# Core.net
KiCad netlist of a schematic drawn in Altium Designer
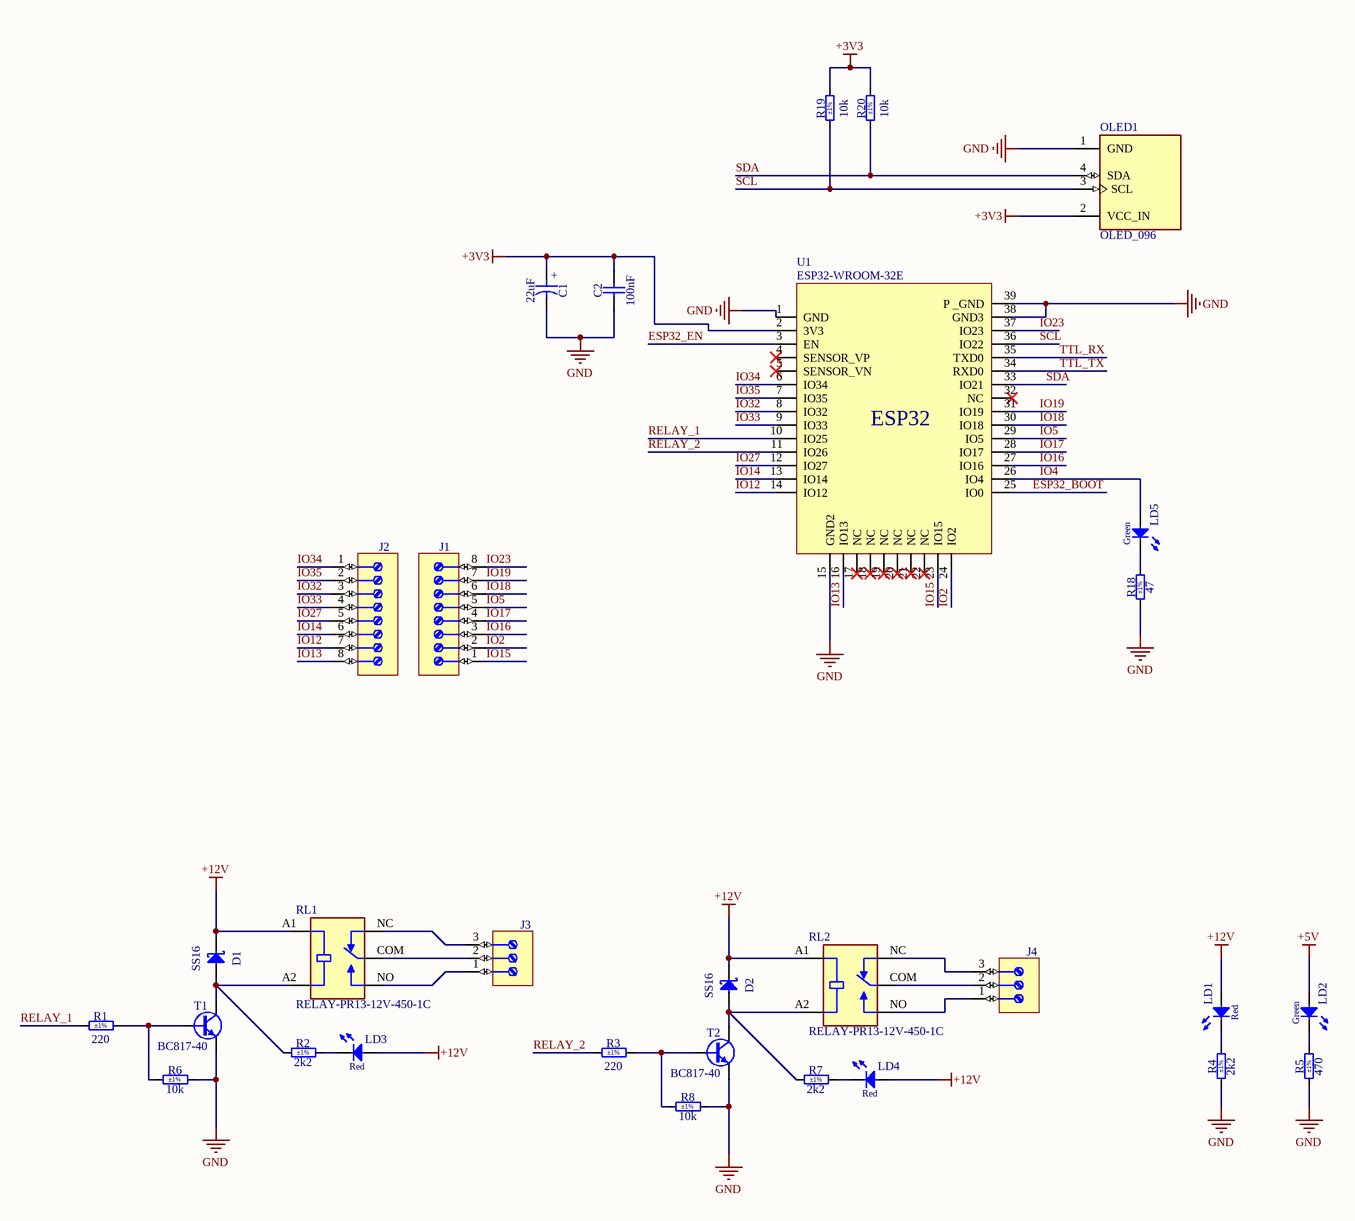
[diagram p0: Core.SchDoc]

(export (version "E")
  (design (tool "Eeschema 10.0.6"))
  (components
    (comp (ref "C1")
      (value "22uF")
      (footprint "CAPMP3528X210N")
      (description "Polarised capacitor")
      (fields
        (field (name "PART NUMBER") "CTE3528-21_22UF_10V_10%_LESR0700")
        (field (name "VOLTAGE") "10V")
        (field (name "AUTHOR") "CERN DEM JLC")
      )
      (libsource (lib "Capacitors") (part "Capacitor - polarized"))
    )
    (comp (ref "C2")
      (value "100nF")
      (footprint "CAPC1608X87N")
      (description "Non-polarised capacitor")
      (fields
        (field (name "PART NUMBER") "CC0603_100NF_50V_10%_X5R")
        (field (name "VOLTAGE") "50V")
        (field (name "AUTHOR") "CERN DEM MR")
      )
      (libsource (lib "Capacitors") (part "Capacitor - non polarized"))
    )
    (comp (ref "D1")
      (value "SS16")
      (footprint "DIOM5127X229N")
      (description "Schottky Diode")
      (fields
        (field (name "VOLTAGE") "60V")
        (field (name "POWER") "1A")
        (field (name "AUTHOR") "CERN DEM JLC")
      )
      (libsource (lib "ICs And Semiconductors") (part "Diode Schottky"))
    )
    (comp (ref "D2")
      (value "SS16")
      (footprint "DIOM5127X229N")
      (description "Schottky Diode")
      (fields
        (field (name "VOLTAGE") "60V")
        (field (name "POWER") "1A")
        (field (name "AUTHOR") "CERN DEM JLC")
      )
      (libsource (lib "ICs And Semiconductors") (part "Diode Schottky"))
    )
    (comp (ref "J1")
      (value "~")
      (footprint "PHOENIX_1715789")
      (description "Terminal Block, 8 Positions, Screw Connection")
      (fields
        (field (name "PART NUMBER") "PHOENIX_1715789")
        (field (name "MANUFACTURER") "PHOENIX CONTACT")
        (field (name "AUTHOR") "CERN DEM JMW")
      )
      (libsource (lib "") (part "Terminal Block_8 Positions_Screw Connection_1"))
    )
    (comp (ref "J2")
      (value "~")
      (footprint "PHOENIX_1715789")
      (description "Terminal Block, 8 Positions, Screw Connection")
      (fields
        (field (name "PART NUMBER") "PHOENIX_1715789")
        (field (name "MANUFACTURER") "PHOENIX CONTACT")
        (field (name "AUTHOR") "CERN DEM JMW")
      )
      (libsource (lib "Connectors") (part "Terminal Block_8 Positions_Screw Connection"))
    )
    (comp (ref "J3")
      (value "~")
      (footprint "PHOENIX_1715734")
      (description "Terminal Block, 3 Positions, Screw Connection")
      (fields
        (field (name "PART NUMBER") "PHOENIX_1715734")
        (field (name "MANUFACTURER") "PHOENIX CONTACT")
        (field (name "AUTHOR") "CERN DEM JLC")
      )
      (libsource (lib "Connectors") (part "Terminal Block_3 Positions_Screw Connection"))
    )
    (comp (ref "J4")
      (value "~")
      (footprint "PHOENIX_1715734")
      (description "Terminal Block, 3 Positions, Screw Connection")
      (fields
        (field (name "PART NUMBER") "PHOENIX_1715734")
        (field (name "MANUFACTURER") "PHOENIX CONTACT")
        (field (name "AUTHOR") "CERN DEM JLC")
      )
      (libsource (lib "Connectors") (part "Terminal Block_3 Positions_Screw Connection"))
    )
    (comp (ref "LD1")
      (value "Red")
      (footprint "LED_KINGBRIGHT_KPH-1608SURCK")
      (description "LED Red 1C 2A")
      (fields
        (field (name "PART NUMBER") "LED_KINGBRIGHT_KPH-1608SURCK")
        (field (name "MANUFACTURER") "KINGBRIGHT")
        (field (name "AUTHOR") "CERN DEM JLC")
      )
      (libsource (lib "ICs And Semiconductors") (part "LED Red 1C 2A"))
    )
    (comp (ref "LD2")
      (value "Green")
      (footprint "LED_KINGBRIGHT_KP-1608CGCK")
      (description "LED Green 1C 2A")
      (fields
        (field (name "PART NUMBER") "LED_KINGBRIGHT_KP-1608CGCK")
        (field (name "MANUFACTURER") "KINGBRIGHT")
        (field (name "AUTHOR") "CERN DEM HF")
      )
      (libsource (lib "ICs And Semiconductors") (part "LED Green 1C 2A"))
    )
    (comp (ref "LD3")
      (value "Red")
      (footprint "LED_KINGBRIGHT_KPH-1608SURCK")
      (description "LED Red 1C 2A")
      (fields
        (field (name "PART NUMBER") "LED_KINGBRIGHT_KPH-1608SURCK")
        (field (name "MANUFACTURER") "KINGBRIGHT")
        (field (name "AUTHOR") "CERN DEM JLC")
      )
      (libsource (lib "ICs And Semiconductors") (part "LED Red 1C 2A"))
    )
    (comp (ref "LD4")
      (value "Red")
      (footprint "LED_KINGBRIGHT_KPH-1608SURCK")
      (description "LED Red 1C 2A")
      (fields
        (field (name "PART NUMBER") "LED_KINGBRIGHT_KPH-1608SURCK")
        (field (name "MANUFACTURER") "KINGBRIGHT")
        (field (name "AUTHOR") "CERN DEM JLC")
      )
      (libsource (lib "ICs And Semiconductors") (part "LED Red 1C 2A"))
    )
    (comp (ref "LD5")
      (value "Green")
      (footprint "LED_KINGBRIGHT_KP-1608CGCK")
      (description "LED Green 1C 2A")
      (fields
        (field (name "PART NUMBER") "LED_KINGBRIGHT_KP-1608CGCK")
        (field (name "MANUFACTURER") "KINGBRIGHT")
        (field (name "AUTHOR") "CERN DEM HF")
      )
      (libsource (lib "ICs And Semiconductors") (part "LED Green 1C 2A"))
    )
    (comp (ref "OLED1")
      (value "OLED_096")
      (footprint "OLED096")
      (libsource (lib "Schlib1") (part "OLED_096"))
    )
    (comp (ref "R1")
      (value "220")
      (footprint "RESC1608X55N")
      (description "Resistor - 1%")
      (fields
        (field (name "TOLERANCE") "±1%")
        (field (name "PART NUMBER") "R0603_220R_1%_0.1W_100PPM")
        (field (name "POWER") "0.1W")
        (field (name "AUTHOR") "CERN DEM JLC")
      )
      (libsource (lib "Resistors") (part "Resistor - 1%"))
    )
    (comp (ref "R2")
      (value "2k2")
      (footprint "RESC1608X55N")
      (description "Resistor - 1%")
      (fields
        (field (name "TOLERANCE") "±1%")
        (field (name "PART NUMBER") "R0603_2K2_1%_0.1W_100PPM")
        (field (name "POWER") "0.1W")
        (field (name "AUTHOR") "CERN DEM JLC")
      )
      (libsource (lib "Resistors") (part "Resistor - 1%"))
    )
    (comp (ref "R3")
      (value "220")
      (footprint "RESC1608X55N")
      (description "Resistor - 1%")
      (fields
        (field (name "TOLERANCE") "±1%")
        (field (name "PART NUMBER") "R0603_220R_1%_0.1W_100PPM")
        (field (name "POWER") "0.1W")
        (field (name "AUTHOR") "CERN DEM JLC")
      )
      (libsource (lib "Resistors") (part "Resistor - 1%"))
    )
    (comp (ref "R4")
      (value "2k2")
      (footprint "RESC1608X55N")
      (description "Resistor - 1%")
      (fields
        (field (name "TOLERANCE") "±1%")
        (field (name "PART NUMBER") "R0603_2K2_1%_0.1W_100PPM")
        (field (name "POWER") "0.1W")
        (field (name "AUTHOR") "CERN DEM JLC")
      )
      (libsource (lib "Resistors") (part "Resistor - 1%"))
    )
    (comp (ref "R5")
      (value "470")
      (footprint "RESC1608X55N")
      (description "Resistor - 1%")
      (fields
        (field (name "TOLERANCE") "±1%")
        (field (name "PART NUMBER") "R0603_470R_1%_0.1W_100PPM")
        (field (name "POWER") "0.1W")
        (field (name "AUTHOR") "CERN DEM JLC")
      )
      (libsource (lib "Resistors") (part "Resistor - 1%"))
    )
    (comp (ref "R6")
      (value "10k")
      (footprint "RESC1608X55N")
      (description "Resistor - 1%")
      (fields
        (field (name "TOLERANCE") "±1%")
        (field (name "PART NUMBER") "R0603_10K_1%_0.1W_100PPM")
        (field (name "POWER") "0.1W")
        (field (name "AUTHOR") "CERN DEM JLC")
      )
      (libsource (lib "Resistors") (part "Resistor - 1%"))
    )
    (comp (ref "R7")
      (value "2k2")
      (footprint "RESC1608X55N")
      (description "Resistor - 1%")
      (fields
        (field (name "TOLERANCE") "±1%")
        (field (name "PART NUMBER") "R0603_2K2_1%_0.1W_100PPM")
        (field (name "POWER") "0.1W")
        (field (name "AUTHOR") "CERN DEM JLC")
      )
      (libsource (lib "Resistors") (part "Resistor - 1%"))
    )
    (comp (ref "R8")
      (value "10k")
      (footprint "RESC1608X55N")
      (description "Resistor - 1%")
      (fields
        (field (name "TOLERANCE") "±1%")
        (field (name "PART NUMBER") "R0603_10K_1%_0.1W_100PPM")
        (field (name "POWER") "0.1W")
        (field (name "AUTHOR") "CERN DEM JLC")
      )
      (libsource (lib "Resistors") (part "Resistor - 1%"))
    )
    (comp (ref "R18")
      (value "47")
      (footprint "RESC1608X55N")
      (description "Resistor - 1%")
      (fields
        (field (name "TOLERANCE") "±1%")
        (field (name "PART NUMBER") "R0603_47R_1%_0.1W_100PPM")
        (field (name "POWER") "0.1W")
        (field (name "AUTHOR") "CERN DEM JLC")
      )
      (libsource (lib "Resistors") (part "Resistor - 1%"))
    )
    (comp (ref "R19")
      (value "10k")
      (footprint "RESC1608X55N")
      (description "Resistor - 1%")
      (fields
        (field (name "TOLERANCE") "±1%")
        (field (name "PART NUMBER") "R0603_10K_1%_0.1W_100PPM")
        (field (name "POWER") "0.1W")
        (field (name "AUTHOR") "CERN DEM JLC")
      )
      (libsource (lib "Resistors") (part "Resistor - 1%"))
    )
    (comp (ref "R20")
      (value "10k")
      (footprint "RESC1608X55N")
      (description "Resistor - 1%")
      (fields
        (field (name "TOLERANCE") "±1%")
        (field (name "PART NUMBER") "R0603_10K_1%_0.1W_100PPM")
        (field (name "POWER") "0.1W")
        (field (name "AUTHOR") "CERN DEM JLC")
      )
      (libsource (lib "Resistors") (part "Resistor - 1%"))
    )
    (comp (ref "RL1")
      (value "RELAY-PR13-12V-450-1C")
      (footprint "RELAY_PR13-12V-450-1C")
      (libsource (lib "Schlib1") (part "RELAY-PR13-12V-450-1C"))
    )
    (comp (ref "RL2")
      (value "RELAY-PR13-12V-450-1C")
      (footprint "RELAY_PR13-12V-450-1C")
      (libsource (lib "Schlib1") (part "RELAY-PR13-12V-450-1C"))
    )
    (comp (ref "T1")
      (value "BC817-40")
      (footprint "SOT95P230X110-3N")
      (description "NPN Transistor")
      (fields (field (name "MANUFACTURER") "NXP SEMICONDUCTORS") (field (name "AUTHOR") "CERN DEM BC"))
      (libsource (lib "ICs And Semiconductors") (part "NPN B1 E2 C3"))
    )
    (comp (ref "T2")
      (value "BC817-40")
      (footprint "SOT95P230X110-3N")
      (description "NPN Transistor")
      (fields (field (name "MANUFACTURER") "NXP SEMICONDUCTORS") (field (name "AUTHOR") "CERN DEM BC"))
      (libsource (lib "ICs And Semiconductors") (part "NPN B1 E2 C3"))
    )
    (comp (ref "U1")
      (value "ESP32-WROOM-32E")
      (footprint "ESP32")
      (libsource (lib "Schlib1") (part "ESP32-WROOM-32E"))
    )
  )
  (nets
    (net (code "1") (name "+3V3") (class "Default")
      (node (ref "C1") (pin "1") (pinfunction "1_1") (pintype "passive"))
      (node (ref "C2") (pin "2") (pinfunction "2_2") (pintype "passive"))
      (node (ref "OLED1") (pin "2") (pinfunction "VCC_IN_2") (pintype "power_in"))
      (node (ref "R19") (pin "2") (pinfunction "2_2") (pintype "passive"))
      (node (ref "R20") (pin "2") (pinfunction "2_2") (pintype "passive"))
      (node (ref "U1") (pin "2") (pinfunction "3V3_2") (pintype "passive"))
    )
    (net (code "2") (name "+5V") (class "Default")
      (node (ref "LD2") (pin "2") (pinfunction "A_2") (pintype "passive"))
    )
    (net (code "3") (name "+12V") (class "Default")
      (node (ref "D1") (pin "1") (pinfunction "C_1") (pintype "passive"))
      (node (ref "D2") (pin "1") (pinfunction "C_1") (pintype "passive"))
      (node (ref "LD1") (pin "2") (pinfunction "A_2") (pintype "passive"))
      (node (ref "LD3") (pin "2") (pinfunction "A_2") (pintype "passive"))
      (node (ref "LD4") (pin "2") (pinfunction "A_2") (pintype "passive"))
      (node (ref "RL1") (pin "A1") (pinfunction "COIL1_A1") (pintype "passive"))
      (node (ref "RL2") (pin "A1") (pinfunction "COIL1_A1") (pintype "passive"))
    )
    (net (code "4") (name "/ESP32_BOOT") (class "Default")
      (node (ref "U1") (pin "25") (pinfunction "IO0_25") (pintype "passive"))
    )
    (net (code "5") (name "/ESP32_EN") (class "Default")
      (node (ref "U1") (pin "3") (pinfunction "EN_3") (pintype "passive"))
    )
    (net (code "6") (name "/IO2") (class "Default")
      (node (ref "J1") (pin "2") (pinfunction "2_2") (pintype "bidirectional"))
      (node (ref "U1") (pin "24") (pinfunction "IO2_24") (pintype "passive"))
    )
    (net (code "7") (name "/IO4") (class "Default")
      (node (ref "LD5") (pin "2") (pinfunction "A_2") (pintype "passive"))
      (node (ref "U1") (pin "26") (pinfunction "IO4_26") (pintype "passive"))
    )
    (net (code "8") (name "/IO5") (class "Default")
      (node (ref "J1") (pin "5") (pinfunction "5_5") (pintype "bidirectional"))
      (node (ref "U1") (pin "29") (pinfunction "IO5_29") (pintype "passive"))
    )
    (net (code "9") (name "/IO12") (class "Default")
      (node (ref "J2") (pin "7") (pinfunction "7_7") (pintype "bidirectional"))
      (node (ref "U1") (pin "14") (pinfunction "IO12_14") (pintype "passive"))
    )
    (net (code "10") (name "/IO13") (class "Default")
      (node (ref "J2") (pin "8") (pinfunction "8_8") (pintype "bidirectional"))
      (node (ref "U1") (pin "16") (pinfunction "IO13_16") (pintype "passive"))
    )
    (net (code "11") (name "/IO14") (class "Default")
      (node (ref "J2") (pin "6") (pinfunction "6_6") (pintype "bidirectional"))
      (node (ref "U1") (pin "13") (pinfunction "IO14_13") (pintype "passive"))
    )
    (net (code "12") (name "/IO15") (class "Default")
      (node (ref "J1") (pin "1") (pinfunction "1_1") (pintype "bidirectional"))
      (node (ref "U1") (pin "23") (pinfunction "IO15_23") (pintype "passive"))
    )
    (net (code "13") (name "/IO16") (class "Default")
      (node (ref "J1") (pin "3") (pinfunction "3_3") (pintype "bidirectional"))
      (node (ref "U1") (pin "27") (pinfunction "IO16_27") (pintype "passive"))
    )
    (net (code "14") (name "/IO17") (class "Default")
      (node (ref "J1") (pin "4") (pinfunction "4_4") (pintype "bidirectional"))
      (node (ref "U1") (pin "28") (pinfunction "IO17_28") (pintype "passive"))
    )
    (net (code "15") (name "/IO18") (class "Default")
      (node (ref "J1") (pin "6") (pinfunction "6_6") (pintype "bidirectional"))
      (node (ref "U1") (pin "30") (pinfunction "IO18_30") (pintype "passive"))
    )
    (net (code "16") (name "/IO19") (class "Default")
      (node (ref "J1") (pin "7") (pinfunction "7_7") (pintype "bidirectional"))
      (node (ref "U1") (pin "31") (pinfunction "IO19_31") (pintype "passive"))
    )
    (net (code "17") (name "/IO23") (class "Default")
      (node (ref "J1") (pin "8") (pinfunction "8_8") (pintype "bidirectional"))
      (node (ref "U1") (pin "37") (pinfunction "IO23_37") (pintype "passive"))
    )
    (net (code "18") (name "/IO27") (class "Default")
      (node (ref "J2") (pin "5") (pinfunction "5_5") (pintype "bidirectional"))
      (node (ref "U1") (pin "12") (pinfunction "IO27_12") (pintype "passive"))
    )
    (net (code "19") (name "/IO32") (class "Default")
      (node (ref "J2") (pin "3") (pinfunction "3_3") (pintype "bidirectional"))
      (node (ref "U1") (pin "8") (pinfunction "IO32_8") (pintype "passive"))
    )
    (net (code "20") (name "/IO33") (class "Default")
      (node (ref "J2") (pin "4") (pinfunction "4_4") (pintype "bidirectional"))
      (node (ref "U1") (pin "9") (pinfunction "IO33_9") (pintype "passive"))
    )
    (net (code "21") (name "/IO34") (class "Default")
      (node (ref "J2") (pin "1") (pinfunction "1_1") (pintype "bidirectional"))
      (node (ref "U1") (pin "6") (pinfunction "IO34_6") (pintype "passive"))
    )
    (net (code "22") (name "/IO35") (class "Default")
      (node (ref "J2") (pin "2") (pinfunction "2_2") (pintype "bidirectional"))
      (node (ref "U1") (pin "7") (pinfunction "IO35_7") (pintype "passive"))
    )
    (net (code "23") (name "/RELAY_1") (class "Default")
      (node (ref "R1") (pin "1") (pinfunction "1_1") (pintype "passive"))
      (node (ref "U1") (pin "10") (pinfunction "IO25_10") (pintype "passive"))
    )
    (net (code "24") (name "/RELAY_2") (class "Default")
      (node (ref "R3") (pin "1") (pinfunction "1_1") (pintype "passive"))
      (node (ref "U1") (pin "11") (pinfunction "IO26_11") (pintype "passive"))
    )
    (net (code "25") (name "/SCL") (class "Default")
      (node (ref "OLED1") (pin "3") (pinfunction "SCL_3") (pintype "input"))
      (node (ref "R19") (pin "1") (pinfunction "1_1") (pintype "passive"))
      (node (ref "U1") (pin "36") (pinfunction "IO22_36") (pintype "passive"))
    )
    (net (code "26") (name "/SDA") (class "Default")
      (node (ref "OLED1") (pin "4") (pinfunction "SDA_4") (pintype "bidirectional"))
      (node (ref "R20") (pin "1") (pinfunction "1_1") (pintype "passive"))
      (node (ref "U1") (pin "33") (pinfunction "IO21_33") (pintype "passive"))
    )
    (net (code "27") (name "/TTL_RX") (class "Default")
      (node (ref "U1") (pin "35") (pinfunction "TXD0_35") (pintype "passive"))
    )
    (net (code "28") (name "/TTL_TX") (class "Default")
      (node (ref "U1") (pin "34") (pinfunction "RXD0_34") (pintype "passive"))
    )
    (net (code "29") (name "GND") (class "Default")
      (node (ref "C1") (pin "2") (pinfunction "2_2") (pintype "passive"))
      (node (ref "C2") (pin "1") (pinfunction "1_1") (pintype "passive"))
      (node (ref "OLED1") (pin "1") (pinfunction "GND_1") (pintype "power_in"))
      (node (ref "R18") (pin "1") (pinfunction "1_1") (pintype "passive"))
      (node (ref "R4") (pin "1") (pinfunction "1_1") (pintype "passive"))
      (node (ref "R5") (pin "1") (pinfunction "1_1") (pintype "passive"))
      (node (ref "R6") (pin "2") (pinfunction "2_2") (pintype "passive"))
      (node (ref "R8") (pin "2") (pinfunction "2_2") (pintype "passive"))
      (node (ref "T1") (pin "2") (pinfunction "E_2") (pintype "passive"))
      (node (ref "T2") (pin "2") (pinfunction "E_2") (pintype "passive"))
      (node (ref "U1") (pin "1") (pinfunction "GND_1") (pintype "passive"))
      (node (ref "U1") (pin "15") (pinfunction "GND2_15") (pintype "passive"))
      (node (ref "U1") (pin "38") (pinfunction "GND3_38") (pintype "passive"))
      (node (ref "U1") (pin "39") (pinfunction "P__GND_39") (pintype "passive"))
    )
    (net (code "30") (name "Net-(D1-A)") (class "Default")
      (node (ref "D1") (pin "2") (pinfunction "A_2") (pintype "passive"))
      (node (ref "R2") (pin "1") (pinfunction "1_1") (pintype "passive"))
      (node (ref "RL1") (pin "A2") (pinfunction "COIL2_A2") (pintype "passive"))
      (node (ref "T1") (pin "3") (pinfunction "C_3") (pintype "passive"))
    )
    (net (code "31") (name "Net-(D2-A)") (class "Default")
      (node (ref "D2") (pin "2") (pinfunction "A_2") (pintype "passive"))
      (node (ref "R7") (pin "1") (pinfunction "1_1") (pintype "passive"))
      (node (ref "RL2") (pin "A2") (pinfunction "COIL2_A2") (pintype "passive"))
      (node (ref "T2") (pin "3") (pinfunction "C_3") (pintype "passive"))
    )
    (net (code "32") (name "Net-(J3-Pad1)") (class "Default")
      (node (ref "J3") (pin "1") (pinfunction "1_1") (pintype "bidirectional"))
      (node (ref "RL1") (pin "NO") (pinfunction "NO_NO") (pintype "passive"))
    )
    (net (code "33") (name "Net-(J3-Pad2)") (class "Default")
      (node (ref "J3") (pin "2") (pinfunction "2_2") (pintype "bidirectional"))
      (node (ref "RL1") (pin "COM") (pinfunction "COM_COM") (pintype "passive"))
    )
    (net (code "34") (name "Net-(J3-Pad3)") (class "Default")
      (node (ref "J3") (pin "3") (pinfunction "3_3") (pintype "bidirectional"))
      (node (ref "RL1") (pin "NC") (pinfunction "NC_NC") (pintype "passive"))
    )
    (net (code "35") (name "Net-(J4-Pad1)") (class "Default")
      (node (ref "J4") (pin "1") (pinfunction "1_1") (pintype "bidirectional"))
      (node (ref "RL2") (pin "NO") (pinfunction "NO_NO") (pintype "passive"))
    )
    (net (code "36") (name "Net-(J4-Pad2)") (class "Default")
      (node (ref "J4") (pin "2") (pinfunction "2_2") (pintype "bidirectional"))
      (node (ref "RL2") (pin "COM") (pinfunction "COM_COM") (pintype "passive"))
    )
    (net (code "37") (name "Net-(J4-Pad3)") (class "Default")
      (node (ref "J4") (pin "3") (pinfunction "3_3") (pintype "bidirectional"))
      (node (ref "RL2") (pin "NC") (pinfunction "NC_NC") (pintype "passive"))
    )
    (net (code "38") (name "Net-(LD1-C)") (class "Default")
      (node (ref "LD1") (pin "1") (pinfunction "C_1") (pintype "passive"))
      (node (ref "R4") (pin "2") (pinfunction "2_2") (pintype "passive"))
    )
    (net (code "39") (name "Net-(LD2-C)") (class "Default")
      (node (ref "LD2") (pin "1") (pinfunction "C_1") (pintype "passive"))
      (node (ref "R5") (pin "2") (pinfunction "2_2") (pintype "passive"))
    )
    (net (code "40") (name "Net-(LD3-C)") (class "Default")
      (node (ref "LD3") (pin "1") (pinfunction "C_1") (pintype "passive"))
      (node (ref "R2") (pin "2") (pinfunction "2_2") (pintype "passive"))
    )
    (net (code "41") (name "Net-(LD4-C)") (class "Default")
      (node (ref "LD4") (pin "1") (pinfunction "C_1") (pintype "passive"))
      (node (ref "R7") (pin "2") (pinfunction "2_2") (pintype "passive"))
    )
    (net (code "42") (name "Net-(LD5-C)") (class "Default")
      (node (ref "LD5") (pin "1") (pinfunction "C_1") (pintype "passive"))
      (node (ref "R18") (pin "2") (pinfunction "2_2") (pintype "passive"))
    )
    (net (code "43") (name "Net-(T1-B)") (class "Default")
      (node (ref "R1") (pin "2") (pinfunction "2_2") (pintype "passive"))
      (node (ref "R6") (pin "1") (pinfunction "1_1") (pintype "passive"))
      (node (ref "T1") (pin "1") (pinfunction "B_1") (pintype "passive"))
    )
    (net (code "44") (name "Net-(T2-B)") (class "Default")
      (node (ref "R3") (pin "2") (pinfunction "2_2") (pintype "passive"))
      (node (ref "R8") (pin "1") (pinfunction "1_1") (pintype "passive"))
      (node (ref "T2") (pin "1") (pinfunction "B_1") (pintype "passive"))
    )
    (net (code "45") (name "unconnected-(U1-NC-Pad17)") (class "Default")
      (node (ref "U1") (pin "17") (pinfunction "NC_17") (pintype "passive+no_connect"))
    )
    (net (code "46") (name "unconnected-(U1-NC-Pad18)") (class "Default")
      (node (ref "U1") (pin "18") (pinfunction "NC_18") (pintype "passive+no_connect"))
    )
    (net (code "47") (name "unconnected-(U1-NC-Pad19)") (class "Default")
      (node (ref "U1") (pin "19") (pinfunction "NC_19") (pintype "passive+no_connect"))
    )
    (net (code "48") (name "unconnected-(U1-NC-Pad20)") (class "Default")
      (node (ref "U1") (pin "20") (pinfunction "NC_20") (pintype "passive+no_connect"))
    )
    (net (code "49") (name "unconnected-(U1-NC-Pad21)") (class "Default")
      (node (ref "U1") (pin "21") (pinfunction "NC_21") (pintype "passive+no_connect"))
    )
    (net (code "50") (name "unconnected-(U1-NC-Pad22)") (class "Default")
      (node (ref "U1") (pin "22") (pinfunction "NC_22") (pintype "passive+no_connect"))
    )
    (net (code "51") (name "unconnected-(U1-NC-Pad32)") (class "Default")
      (node (ref "U1") (pin "32") (pinfunction "NC_32") (pintype "passive+no_connect"))
    )
    (net (code "52") (name "unconnected-(U1-SENSOR_VN-Pad5)") (class "Default")
      (node (ref "U1") (pin "5") (pinfunction "SENSOR_VN_5") (pintype "passive+no_connect"))
    )
    (net (code "53") (name "unconnected-(U1-SENSOR_VP-Pad4)") (class "Default")
      (node (ref "U1") (pin "4") (pinfunction "SENSOR_VP_4") (pintype "passive+no_connect"))
    )
  )
)
